# regulated_power_supply.net
KiCad netlist of a schematic drawn in EAGLE
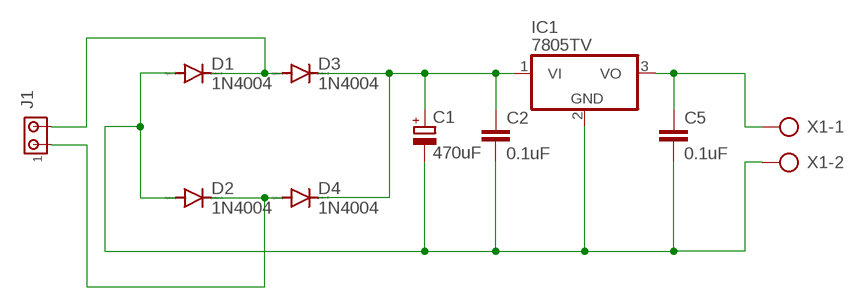
[diagram p0: schematic, sheet 1]

(export (version "E")
  (design (tool "Eeschema 10.0.6"))
  (components
    (comp (ref "C1")
      (value "470uF")
      (footprint "eagle-import:E2,5-7")
      (libsource (lib "eagle-import") (part "CPOL-EUE2.5-7"))
    )
    (comp (ref "C2")
      (value "0.1uF")
      (footprint "eagle-import:C025-050X050")
      (libsource (lib "eagle-import") (part "C-EU025-050X050"))
    )
    (comp (ref "C5")
      (value "0.1uF")
      (footprint "eagle-import:C025-050X050")
      (libsource (lib "eagle-import") (part "C-EU025-050X050"))
    )
    (comp (ref "D1")
      (value "1N4004")
      (footprint "eagle-import:DO41-10")
      (libsource (lib "eagle-import") (part "1N4004"))
    )
    (comp (ref "D2")
      (value "1N4004")
      (footprint "eagle-import:DO41-10")
      (libsource (lib "eagle-import") (part "1N4004"))
    )
    (comp (ref "D3")
      (value "1N4004")
      (footprint "eagle-import:DO41-10")
      (libsource (lib "eagle-import") (part "1N4004"))
    )
    (comp (ref "D4")
      (value "1N4004")
      (footprint "eagle-import:DO41-10")
      (libsource (lib "eagle-import") (part "1N4004"))
    )
    (comp (ref "IC1")
      (value "7805TV")
      (footprint "eagle-import:TO220V")
      (libsource (lib "eagle-import") (part "78TV05"))
    )
    (comp (ref "J1")
      (value "MTA02-100")
      (footprint "eagle-import:10X02MTA")
      (libsource (lib "eagle-import") (part "MTA02-100"))
    )
    (comp (ref "X1")
      (value "AK300/2")
      (footprint "eagle-import:AK300_2")
      (libsource (lib "eagle-import") (part "AK300/2"))
    )
  )
  (nets
    (net (code "1") (name "Net-(D1-PadC)") (class "Default")
      (node (ref "D1") (pin "C") (pinfunction "C_C") (pintype "passive"))
      (node (ref "D3") (pin "A") (pinfunction "A_A") (pintype "passive"))
      (node (ref "J1") (pin "2") (pinfunction "2_2") (pintype "passive"))
    )
    (net (code "2") (name "Net-(D2-PadC)") (class "Default")
      (node (ref "D2") (pin "C") (pinfunction "C_C") (pintype "passive"))
      (node (ref "D4") (pin "A") (pinfunction "A_A") (pintype "passive"))
      (node (ref "J1") (pin "1") (pinfunction "1_1") (pintype "passive"))
    )
    (net (code "3") (name "Net-(IC1-GND)") (class "Default")
      (node (ref "C1") (pin "-") (pinfunction "-_-") (pintype "passive"))
      (node (ref "C2") (pin "2") (pinfunction "2_2") (pintype "passive"))
      (node (ref "C5") (pin "2") (pinfunction "2_2") (pintype "passive"))
      (node (ref "D1") (pin "A") (pinfunction "A_A") (pintype "passive"))
      (node (ref "D2") (pin "A") (pinfunction "A_A") (pintype "passive"))
      (node (ref "IC1") (pin "2") (pinfunction "GND_2") (pintype "passive"))
      (node (ref "X1") (pin "2") (pinfunction "KL_2") (pintype "passive"))
    )
    (net (code "4") (name "Net-(IC1-VI)") (class "Default")
      (node (ref "C1") (pin "+") (pinfunction "+_+") (pintype "passive"))
      (node (ref "C2") (pin "1") (pinfunction "1_1") (pintype "passive"))
      (node (ref "D3") (pin "C") (pinfunction "C_C") (pintype "passive"))
      (node (ref "D4") (pin "C") (pinfunction "C_C") (pintype "passive"))
      (node (ref "IC1") (pin "1") (pinfunction "VI_1") (pintype "input"))
    )
    (net (code "5") (name "Net-(IC1-VO)") (class "Default")
      (node (ref "C5") (pin "1") (pinfunction "1_1") (pintype "passive"))
      (node (ref "IC1") (pin "3") (pinfunction "VO_3") (pintype "passive"))
      (node (ref "X1") (pin "1") (pinfunction "KL_1") (pintype "passive"))
    )
  )
)
